# i2c_dev_blk.net
KiCad netlist of a schematic drawn in Altium Designer
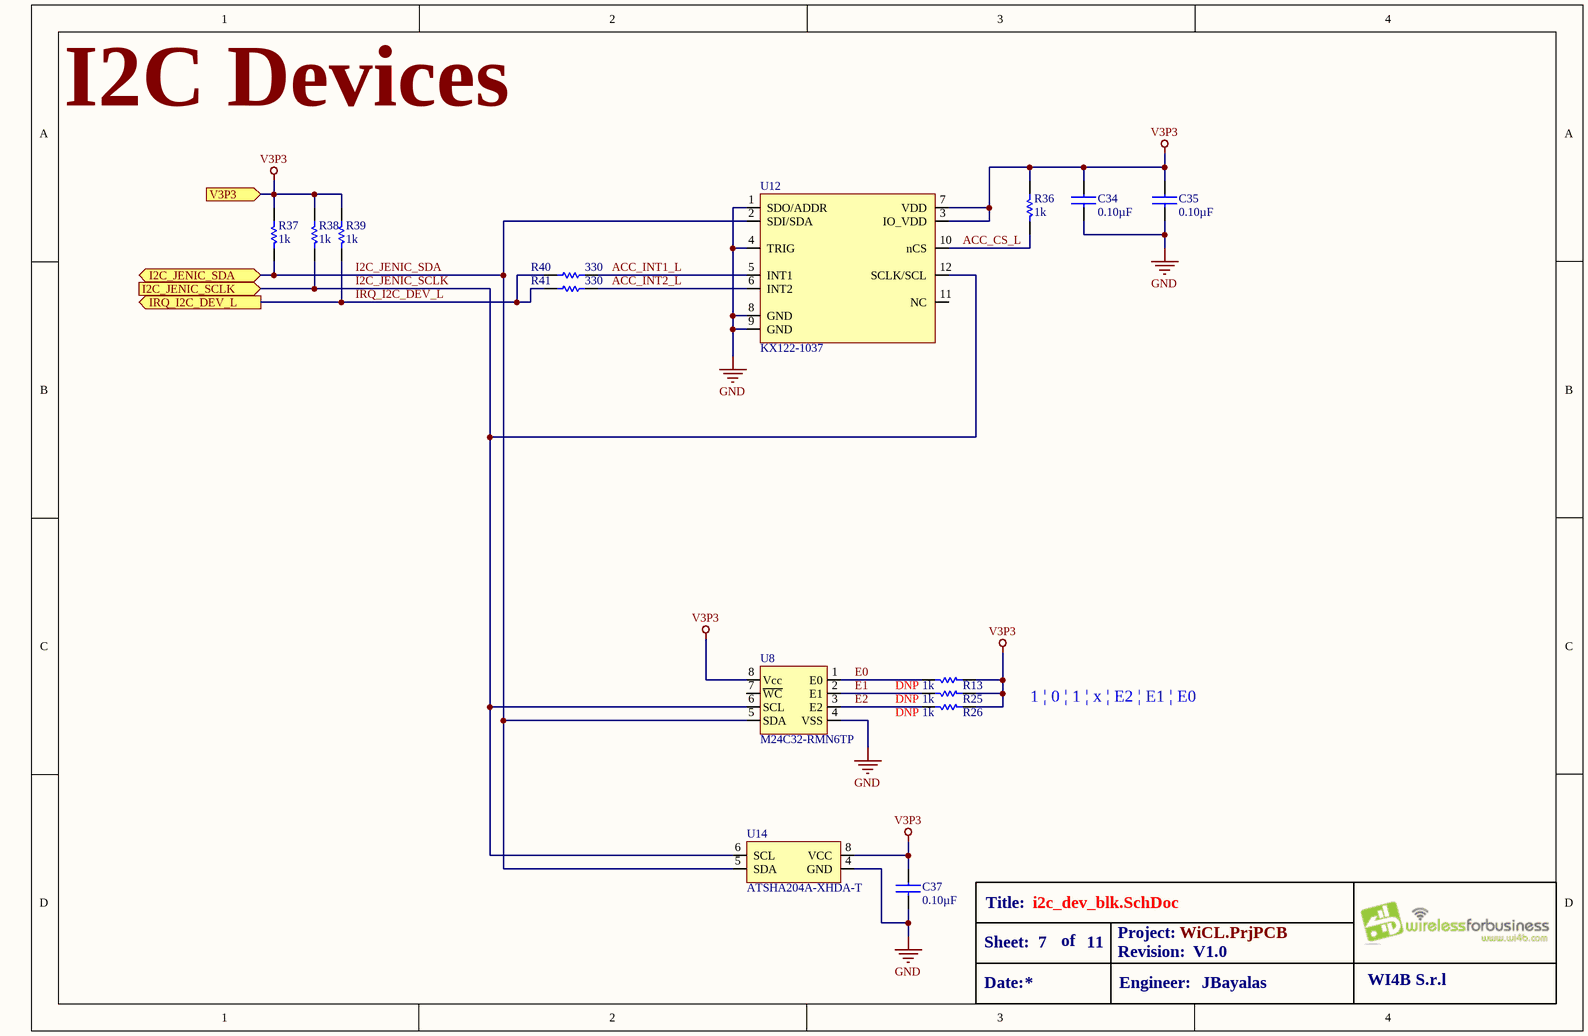
[diagram p0: i2c_dev_blk.SchDoc]

(export (version "E")
  (design (tool "Eeschema 10.0.6"))
  (components
    (comp (ref "C34")
      (value "0.10µF")
      (footprint "C0402")
      (description "CAP CER 0.1UF 50V X7R 0402")
      (fields (field (name "MPN") "GRM155R71H104ME14D"))
      (libsource (lib "Capacitor") (part "GRM155R71H104ME14D"))
    )
    (comp (ref "C35")
      (value "0.10µF")
      (footprint "C0402")
      (description "CAP CER 0.1UF 50V X7R 0402")
      (fields (field (name "MPN") "GRM155R71H104ME14D"))
      (libsource (lib "Capacitor") (part "GRM155R71H104ME14D"))
    )
    (comp (ref "C37")
      (value "0.10µF")
      (footprint "C0402")
      (description "CAP CER 0.1UF 50V X7R 0402")
      (fields (field (name "MPN") "GRM155R71H104ME14D"))
      (libsource (lib "Capacitor") (part "GRM155R71H104ME14D"))
    )
    (comp (ref "R13")
      (value "1k")
      (footprint "R0402")
      (description "RES SMD 1K OHM 1% 1/10W 0402")
      (fields (field (name "MPN") "MCS04020C1001FE000") (field (name "DNP") "DNP"))
      (libsource (lib "Res") (part "MCS04020C1001FE000"))
    )
    (comp (ref "R25")
      (value "1k")
      (footprint "R0402")
      (description "RES SMD 1K OHM 1% 1/10W 0402")
      (fields (field (name "MPN") "MCS04020C1001FE000") (field (name "DNP") "DNP"))
      (libsource (lib "Res") (part "MCS04020C1001FE000"))
    )
    (comp (ref "R26")
      (value "1k")
      (footprint "R0402")
      (description "RES SMD 1K OHM 1% 1/10W 0402")
      (fields (field (name "MPN") "MCS04020C1001FE000") (field (name "DNP") "DNP"))
      (libsource (lib "Res") (part "MCS04020C1001FE000"))
    )
    (comp (ref "R36")
      (value "1k")
      (footprint "R0402")
      (description "RES SMD 1K OHM 1% 1/10W 0402")
      (fields (field (name "MPN") "MCS04020C1001FE000"))
      (libsource (lib "Res") (part "MCS04020C1001FE000"))
    )
    (comp (ref "R37")
      (value "1k")
      (footprint "R0402")
      (description "RES SMD 1K OHM 1% 1/10W 0402")
      (fields (field (name "MPN") "MCS04020C1001FE000"))
      (libsource (lib "Res") (part "MCS04020C1001FE000"))
    )
    (comp (ref "R38")
      (value "1k")
      (footprint "R0402")
      (description "RES SMD 1K OHM 1% 1/10W 0402")
      (fields (field (name "MPN") "MCS04020C1001FE000"))
      (libsource (lib "Res") (part "MCS04020C1001FE000"))
    )
    (comp (ref "R39")
      (value "1k")
      (footprint "R0402")
      (description "RES SMD 1K OHM 1% 1/10W 0402")
      (fields (field (name "MPN") "MCS04020C1001FE000"))
      (libsource (lib "Res") (part "MCS04020C1001FE000"))
    )
    (comp (ref "R40")
      (value "330")
      (footprint "R0402")
      (description "RES SMD 330 OHM 1% 1/16W 0402")
      (fields (field (name "MPN") "CRCW0402330RFKED"))
      (libsource (lib "Res") (part "CRCW0402330RFKED"))
    )
    (comp (ref "R41")
      (value "330")
      (footprint "R0402")
      (description "RES SMD 330 OHM 1% 1/16W 0402")
      (fields (field (name "MPN") "CRCW0402330RFKED"))
      (libsource (lib "Res") (part "CRCW0402330RFKED"))
    )
    (comp (ref "U8")
      (value "M24C32-RMN6TP")
      (footprint "8-SOIC")
      (description "IC EEPROM 32KBIT 400KHZ 8SO")
      (fields (field (name "MPN") "M24C32-RMN6TP"))
      (libsource (lib "IC") (part "M24C32-RMN6TP"))
    )
    (comp (ref "U12")
      (value "KX122-1037")
      (footprint "KX122-1037")
      (description "ACCELEROMETER 2-8G I2C/SPI 12LGA")
      (fields (field (name "MPN") "KX122-1037"))
      (libsource (lib "IC") (part "KX122-1037"))
    )
    (comp (ref "U14")
      (value "ATSHA204A-XHDA-T")
      (footprint "TSSOP-8 (wide Body)")
      (description "IC CRYPTO 4.5KB I2C")
      (fields (field (name "MPN") "ATSHA204A-XHDA-T"))
      (libsource (lib "IC") (part "ATSHA204A-XHDA-T"))
    )
  )
  (nets
    (net (code "1") (name "/ACC_CS_L") (class "Default")
      (node (ref "R36") (pin "1") (pinfunction "1_1") (pintype "passive"))
      (node (ref "U12") (pin "10") (pinfunction "nCS_10") (pintype "passive"))
    )
    (net (code "2") (name "/ACC_INT1_L") (class "Default")
      (node (ref "R40") (pin "1") (pinfunction "1_1") (pintype "passive"))
      (node (ref "U12") (pin "5") (pinfunction "INT1_5") (pintype "passive"))
    )
    (net (code "3") (name "/ACC_INT2_L") (class "Default")
      (node (ref "R41") (pin "1") (pinfunction "1_1") (pintype "passive"))
      (node (ref "U12") (pin "6") (pinfunction "INT2_6") (pintype "passive"))
    )
    (net (code "4") (name "/E0") (class "Default")
      (node (ref "R13") (pin "2") (pinfunction "2_2") (pintype "passive"))
      (node (ref "U8") (pin "1") (pinfunction "E0_1") (pintype "passive"))
    )
    (net (code "5") (name "/E1") (class "Default")
      (node (ref "R25") (pin "2") (pinfunction "2_2") (pintype "passive"))
      (node (ref "U8") (pin "2") (pinfunction "E1_2") (pintype "passive"))
    )
    (net (code "6") (name "/E2") (class "Default")
      (node (ref "R26") (pin "2") (pinfunction "2_2") (pintype "passive"))
      (node (ref "U8") (pin "3") (pinfunction "E2_3") (pintype "passive"))
    )
    (net (code "7") (name "/I2C_JENIC_SCLK") (class "Default")
      (node (ref "R38") (pin "1") (pinfunction "1_1") (pintype "passive"))
      (node (ref "U12") (pin "12") (pinfunction "SCLK/SCL_12") (pintype "passive"))
      (node (ref "U14") (pin "6") (pinfunction "SCL_6") (pintype "passive"))
      (node (ref "U8") (pin "6") (pinfunction "SCL_6") (pintype "passive"))
    )
    (net (code "8") (name "/I2C_JENIC_SDA") (class "Default")
      (node (ref "R37") (pin "1") (pinfunction "1_1") (pintype "passive"))
      (node (ref "U12") (pin "2") (pinfunction "SDI/SDA_2") (pintype "passive"))
      (node (ref "U14") (pin "5") (pinfunction "SDA_5") (pintype "passive"))
      (node (ref "U8") (pin "5") (pinfunction "SDA_5") (pintype "passive"))
    )
    (net (code "9") (name "/IRQ_I2C_DEV_L") (class "Default")
      (node (ref "R39") (pin "1") (pinfunction "1_1") (pintype "passive"))
      (node (ref "R40") (pin "2") (pinfunction "2_2") (pintype "passive"))
      (node (ref "R41") (pin "2") (pinfunction "2_2") (pintype "passive"))
    )
    (net (code "10") (name "GND") (class "Default")
      (node (ref "C34") (pin "2") (pinfunction "2_2") (pintype "passive"))
      (node (ref "C35") (pin "2") (pinfunction "2_2") (pintype "passive"))
      (node (ref "C37") (pin "2") (pinfunction "2_2") (pintype "passive"))
      (node (ref "U12") (pin "1") (pinfunction "SDO/ADDR_1") (pintype "passive"))
      (node (ref "U12") (pin "4") (pinfunction "TRIG_4") (pintype "passive"))
      (node (ref "U12") (pin "8") (pinfunction "GND_8") (pintype "passive"))
      (node (ref "U12") (pin "9") (pinfunction "GND_9") (pintype "passive"))
      (node (ref "U14") (pin "4") (pinfunction "GND_4") (pintype "passive"))
      (node (ref "U8") (pin "4") (pinfunction "VSS_4") (pintype "passive"))
    )
    (net (code "11") (name "V3P3") (class "Default")
      (node (ref "C34") (pin "1") (pinfunction "1_1") (pintype "passive"))
      (node (ref "C35") (pin "1") (pinfunction "1_1") (pintype "passive"))
      (node (ref "C37") (pin "1") (pinfunction "1_1") (pintype "passive"))
      (node (ref "R13") (pin "1") (pinfunction "1_1") (pintype "passive"))
      (node (ref "R25") (pin "1") (pinfunction "1_1") (pintype "passive"))
      (node (ref "R26") (pin "1") (pinfunction "1_1") (pintype "passive"))
      (node (ref "R36") (pin "2") (pinfunction "2_2") (pintype "passive"))
      (node (ref "R37") (pin "2") (pinfunction "2_2") (pintype "passive"))
      (node (ref "R38") (pin "2") (pinfunction "2_2") (pintype "passive"))
      (node (ref "R39") (pin "2") (pinfunction "2_2") (pintype "passive"))
      (node (ref "U12") (pin "3") (pinfunction "IO_VDD_3") (pintype "passive"))
      (node (ref "U12") (pin "7") (pinfunction "VDD_7") (pintype "passive"))
      (node (ref "U14") (pin "8") (pinfunction "VCC_8") (pintype "passive"))
      (node (ref "U8") (pin "8") (pinfunction "Vcc_8") (pintype "passive"))
    )
    (net (code "12") (name "unconnected-(U8-~{WC}-Pad7)") (class "Default")
      (node (ref "U8") (pin "7") (pinfunction "~{WC}_7") (pintype "passive"))
    )
    (net (code "13") (name "unconnected-(U12-NC-Pad11)") (class "Default")
      (node (ref "U12") (pin "11") (pinfunction "NC_11") (pintype "passive"))
    )
  )
)
